# LM2576-v2.net
KiCad netlist of a schematic drawn in Altium Designer
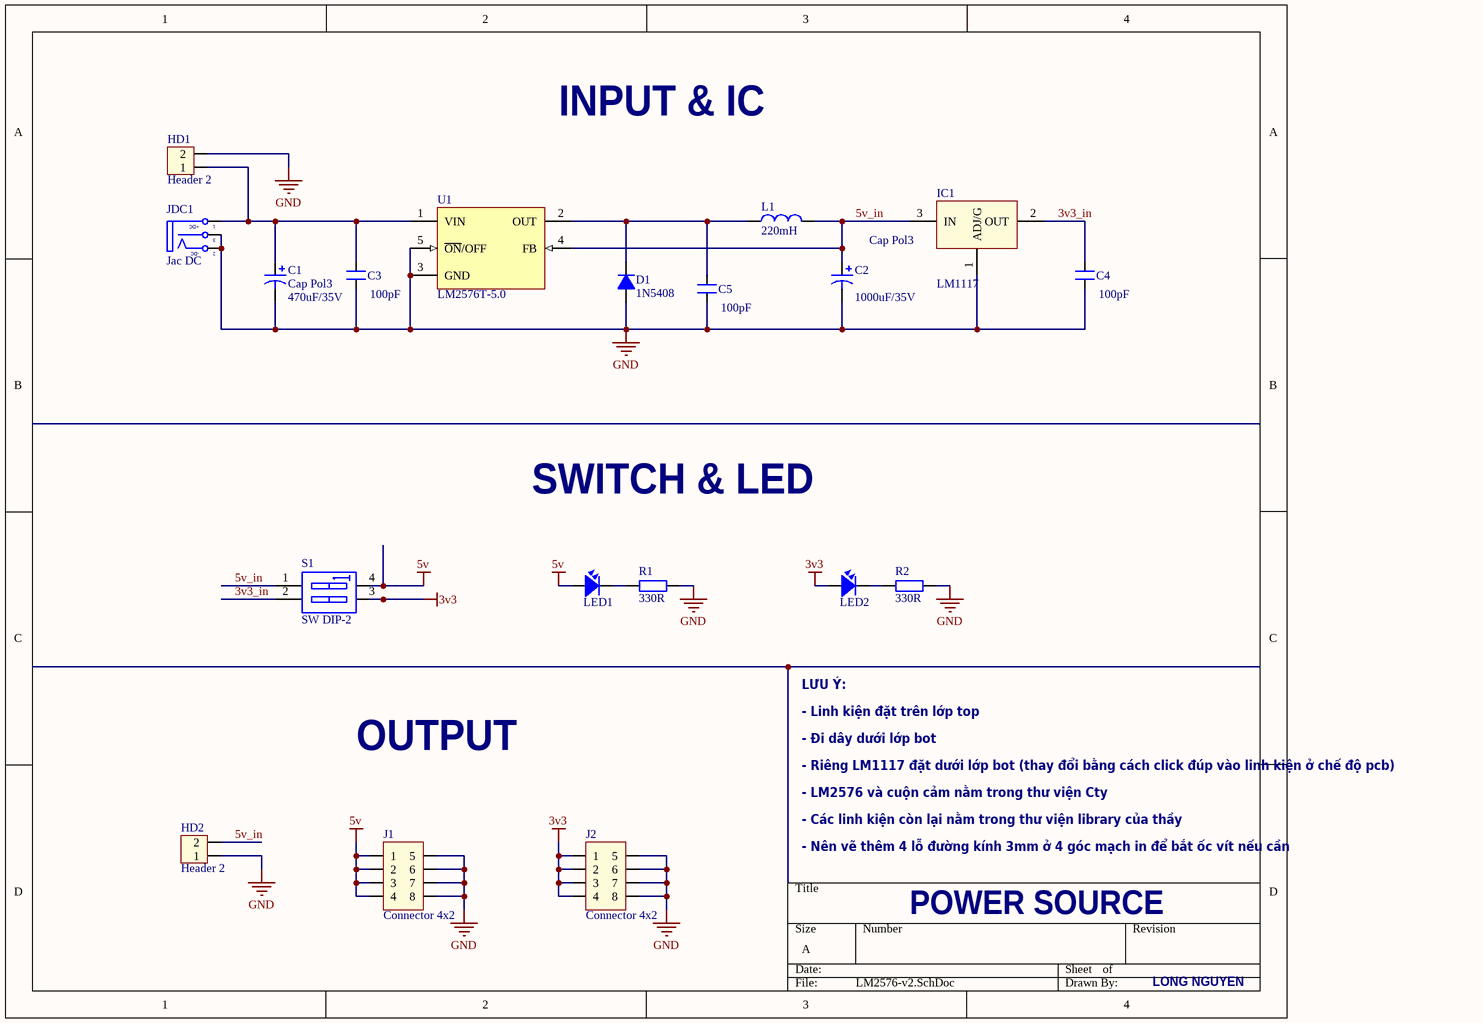
[diagram p0: LM2576-v2.SchDoc]

(export (version "E")
  (design (tool "Eeschema 10.0.6"))
  (components
    (comp (ref "C1")
      (value "Cap Pol3")
      (footprint "CP2/5")
      (description "Polarized Capacitor (Surface Mount)")
      (fields (field (name "ALTIUM_VALUE") "470uF/35V") (field (name "PUBLISHER") "Altium Limited"))
      (libsource (lib "library") (part "Cap Pol3"))
    )
    (comp (ref "C2")
      (value "Cap Pol3")
      (footprint "CP2/5")
      (description "Polarized Capacitor (Surface Mount)")
      (fields (field (name "ALTIUM_VALUE") "1000uF/35V") (field (name "PUBLISHER") "Altium Limited"))
      (libsource (lib "library") (part "Cap Pol3"))
    )
    (comp (ref "C3")
      (value "100pF")
      (footprint "SM-CAP-3225")
      (description "Cap np  1pF - 472pF")
      (libsource (lib "library") (part "CN1"))
    )
    (comp (ref "C4")
      (value "100pF")
      (footprint "SM-CAP-3225")
      (description "Cap np  1pF - 472pF")
      (libsource (lib "library") (part "CN1"))
    )
    (comp (ref "C5")
      (value "100pF")
      (footprint "SM-CAP-3225")
      (description "Cap np  1pF - 472pF")
      (libsource (lib "library") (part "CN1"))
    )
    (comp (ref "D1")
      (value "1N5408")
      (footprint "D5A")
      (description "Diode 5A")
      (libsource (lib "library") (part "D5A"))
    )
    (comp (ref "HD1")
      (value "Header 2")
      (footprint "HED2")
      (description "Header 2 (Green)")
      (libsource (lib "library") (part "Hed2"))
    )
    (comp (ref "HD2")
      (value "Header 2")
      (footprint "HED2")
      (description "Header 2 (Green)")
      (libsource (lib "library") (part "Hed2"))
    )
    (comp (ref "IC1")
      (value "LM1117")
      (footprint "SOT223-4N")
      (description "Available in 1.8V, 2.5V, 2.85V, 3.3V, 5V, and  Adjustable Versions")
      (libsource (lib "library") (part "LM1117"))
    )
    (comp (ref "J1") (value "Connector 4x2") (footprint "JP4x2") (libsource (lib "library") (part "JP4x2")))
    (comp (ref "J2") (value "Connector 4x2") (footprint "JP4x2") (libsource (lib "library") (part "JP4x2")))
    (comp (ref "JDC1")
      (value "Jac DC")
      (footprint "DC-IN")
      (description "Jac DC input")
      (libsource (lib "library") (part "DCIN"))
    )
    (comp (ref "L1")
      (value "220mH")
      (footprint "L01")
      (description "Inductor")
      (libsource (lib "library") (part "L1"))
    )
    (comp (ref "LED1")
      (value "LED")
      (footprint "SM-LED-0805-Red")
      (description "LED Single colour Green and Red")
      (libsource (lib "library") (part "LED"))
    )
    (comp (ref "LED2")
      (value "LED")
      (footprint "SM-LED-0805-Red")
      (description "LED Single colour Green and Red")
      (libsource (lib "library") (part "LED"))
    )
    (comp (ref "R1")
      (value "330R")
      (footprint "SM-RES-1206")
      (description "Resistor 1/4W")
      (libsource (lib "library") (part "R1/4W"))
    )
    (comp (ref "R2")
      (value "330R")
      (footprint "SM-RES-1206")
      (description "Resistor 1/4W")
      (libsource (lib "library") (part "R1/4W"))
    )
    (comp (ref "S1")
      (value "SW DIP-2")
      (footprint "DIPSWITCH2")
      (description "DIP Switch, 2 Position, SPST")
      (fields (field (name "PUBLISHER") "Altium Limited"))
      (libsource (lib "NBBLib-14-03-2012") (part "SW DIP-2"))
    )
    (comp (ref "U1")
      (value "LM2576T-5.0")
      (footprint "LM2576t")
      (description "SIMPLE SWITCHER; 3A Step-Down Voltage Regulator")
      (fields
        (field (name "MANUFACTURER") "National Semiconductor")
        (field (name "DIGIKEYPARTNUMBER") "LM2576T-5.0-ND")
        (field (name "PUBLISHER") "Altium Limited")
      )
      (libsource (lib "Cty1") (part "LM2576T-5.0"))
    )
  )
  (nets
    (net (code "1") (name "/3v3_in") (class "Default")
      (node (ref "C4") (pin "2") (pinfunction "2_2") (pintype "passive"))
      (node (ref "IC1") (pin "2") (pinfunction "OUT_2") (pintype "passive"))
      (node (ref "S1") (pin "2") (pinfunction "A2_2") (pintype "passive"))
    )
    (net (code "2") (name "/5v_in") (class "Default")
      (node (ref "C2") (pin "1") (pinfunction "1_1") (pintype "passive"))
      (node (ref "HD2") (pin "2") (pinfunction "2_2") (pintype "passive"))
      (node (ref "IC1") (pin "3") (pinfunction "IN_3") (pintype "passive"))
      (node (ref "L1") (pin "2") (pinfunction "2_2") (pintype "passive"))
      (node (ref "S1") (pin "1") (pinfunction "A1_1") (pintype "passive"))
      (node (ref "U1") (pin "4") (pinfunction "FB_4") (pintype "input"))
    )
    (net (code "3") (name "3v3") (class "Default")
      (node (ref "J2") (pin "1") (pinfunction "1_1") (pintype "passive"))
      (node (ref "J2") (pin "2") (pinfunction "2_2") (pintype "passive"))
      (node (ref "J2") (pin "3") (pinfunction "3_3") (pintype "passive"))
      (node (ref "J2") (pin "4") (pinfunction "4_4") (pintype "passive"))
      (node (ref "LED2") (pin "1") (pinfunction "1_1") (pintype "passive"))
      (node (ref "S1") (pin "3") (pinfunction "B2_3") (pintype "passive"))
    )
    (net (code "4") (name "5v") (class "Default")
      (node (ref "J1") (pin "1") (pinfunction "1_1") (pintype "passive"))
      (node (ref "J1") (pin "2") (pinfunction "2_2") (pintype "passive"))
      (node (ref "J1") (pin "3") (pinfunction "3_3") (pintype "passive"))
      (node (ref "J1") (pin "4") (pinfunction "4_4") (pintype "passive"))
      (node (ref "LED1") (pin "1") (pinfunction "1_1") (pintype "passive"))
      (node (ref "S1") (pin "4") (pinfunction "B1_4") (pintype "passive"))
    )
    (net (code "5") (name "GND") (class "Default")
      (node (ref "C1") (pin "2") (pinfunction "2_2") (pintype "passive"))
      (node (ref "C2") (pin "2") (pinfunction "2_2") (pintype "passive"))
      (node (ref "C3") (pin "1") (pinfunction "1_1") (pintype "passive"))
      (node (ref "C4") (pin "1") (pinfunction "1_1") (pintype "passive"))
      (node (ref "C5") (pin "1") (pinfunction "1_1") (pintype "passive"))
      (node (ref "D1") (pin "1") (pinfunction "A_1") (pintype "passive"))
      (node (ref "HD1") (pin "2") (pinfunction "2_2") (pintype "passive"))
      (node (ref "HD2") (pin "1") (pinfunction "1_1") (pintype "passive"))
      (node (ref "IC1") (pin "1") (pinfunction "ADJ/G_1") (pintype "passive"))
      (node (ref "J1") (pin "5") (pinfunction "5_5") (pintype "passive"))
      (node (ref "J1") (pin "6") (pinfunction "6_6") (pintype "passive"))
      (node (ref "J1") (pin "7") (pinfunction "7_7") (pintype "passive"))
      (node (ref "J1") (pin "8") (pinfunction "8_8") (pintype "passive"))
      (node (ref "J2") (pin "5") (pinfunction "5_5") (pintype "passive"))
      (node (ref "J2") (pin "6") (pinfunction "6_6") (pintype "passive"))
      (node (ref "J2") (pin "7") (pinfunction "7_7") (pintype "passive"))
      (node (ref "J2") (pin "8") (pinfunction "8_8") (pintype "passive"))
      (node (ref "JDC1") (pin "2") (pinfunction "TN_2") (pintype "passive"))
      (node (ref "JDC1") (pin "3") (pinfunction "S_3") (pintype "power_in"))
      (node (ref "R1") (pin "2") (pinfunction "2_2") (pintype "passive"))
      (node (ref "R2") (pin "2") (pinfunction "2_2") (pintype "passive"))
      (node (ref "U1") (pin "3") (pinfunction "GND_3") (pintype "power_in"))
      (node (ref "U1") (pin "5") (pinfunction "~{ON}/OFF_5") (pintype "input"))
    )
    (net (code "6") (name "Net-(D1-K)") (class "Default")
      (node (ref "C5") (pin "2") (pinfunction "2_2") (pintype "passive"))
      (node (ref "D1") (pin "2") (pinfunction "K_2") (pintype "passive"))
      (node (ref "L1") (pin "1") (pinfunction "1_1") (pintype "passive"))
      (node (ref "U1") (pin "2") (pinfunction "OUT_2") (pintype "power_in"))
    )
    (net (code "7") (name "Net-(JDC1-T)") (class "Default")
      (node (ref "C1") (pin "1") (pinfunction "1_1") (pintype "passive"))
      (node (ref "C3") (pin "2") (pinfunction "2_2") (pintype "passive"))
      (node (ref "HD1") (pin "1") (pinfunction "1_1") (pintype "passive"))
      (node (ref "JDC1") (pin "1") (pinfunction "T_1") (pintype "passive"))
      (node (ref "U1") (pin "1") (pinfunction "VIN_1") (pintype "power_in"))
    )
    (net (code "8") (name "Net-(LED1-Pad2)") (class "Default")
      (node (ref "LED1") (pin "2") (pinfunction "2_2") (pintype "passive"))
      (node (ref "R1") (pin "1") (pinfunction "1_1") (pintype "passive"))
    )
    (net (code "9") (name "Net-(LED2-Pad2)") (class "Default")
      (node (ref "LED2") (pin "2") (pinfunction "2_2") (pintype "passive"))
      (node (ref "R2") (pin "1") (pinfunction "1_1") (pintype "passive"))
    )
  )
)
